# N-CW7_PWR_TWB.net
KiCad netlist of a schematic drawn in Altium Designer
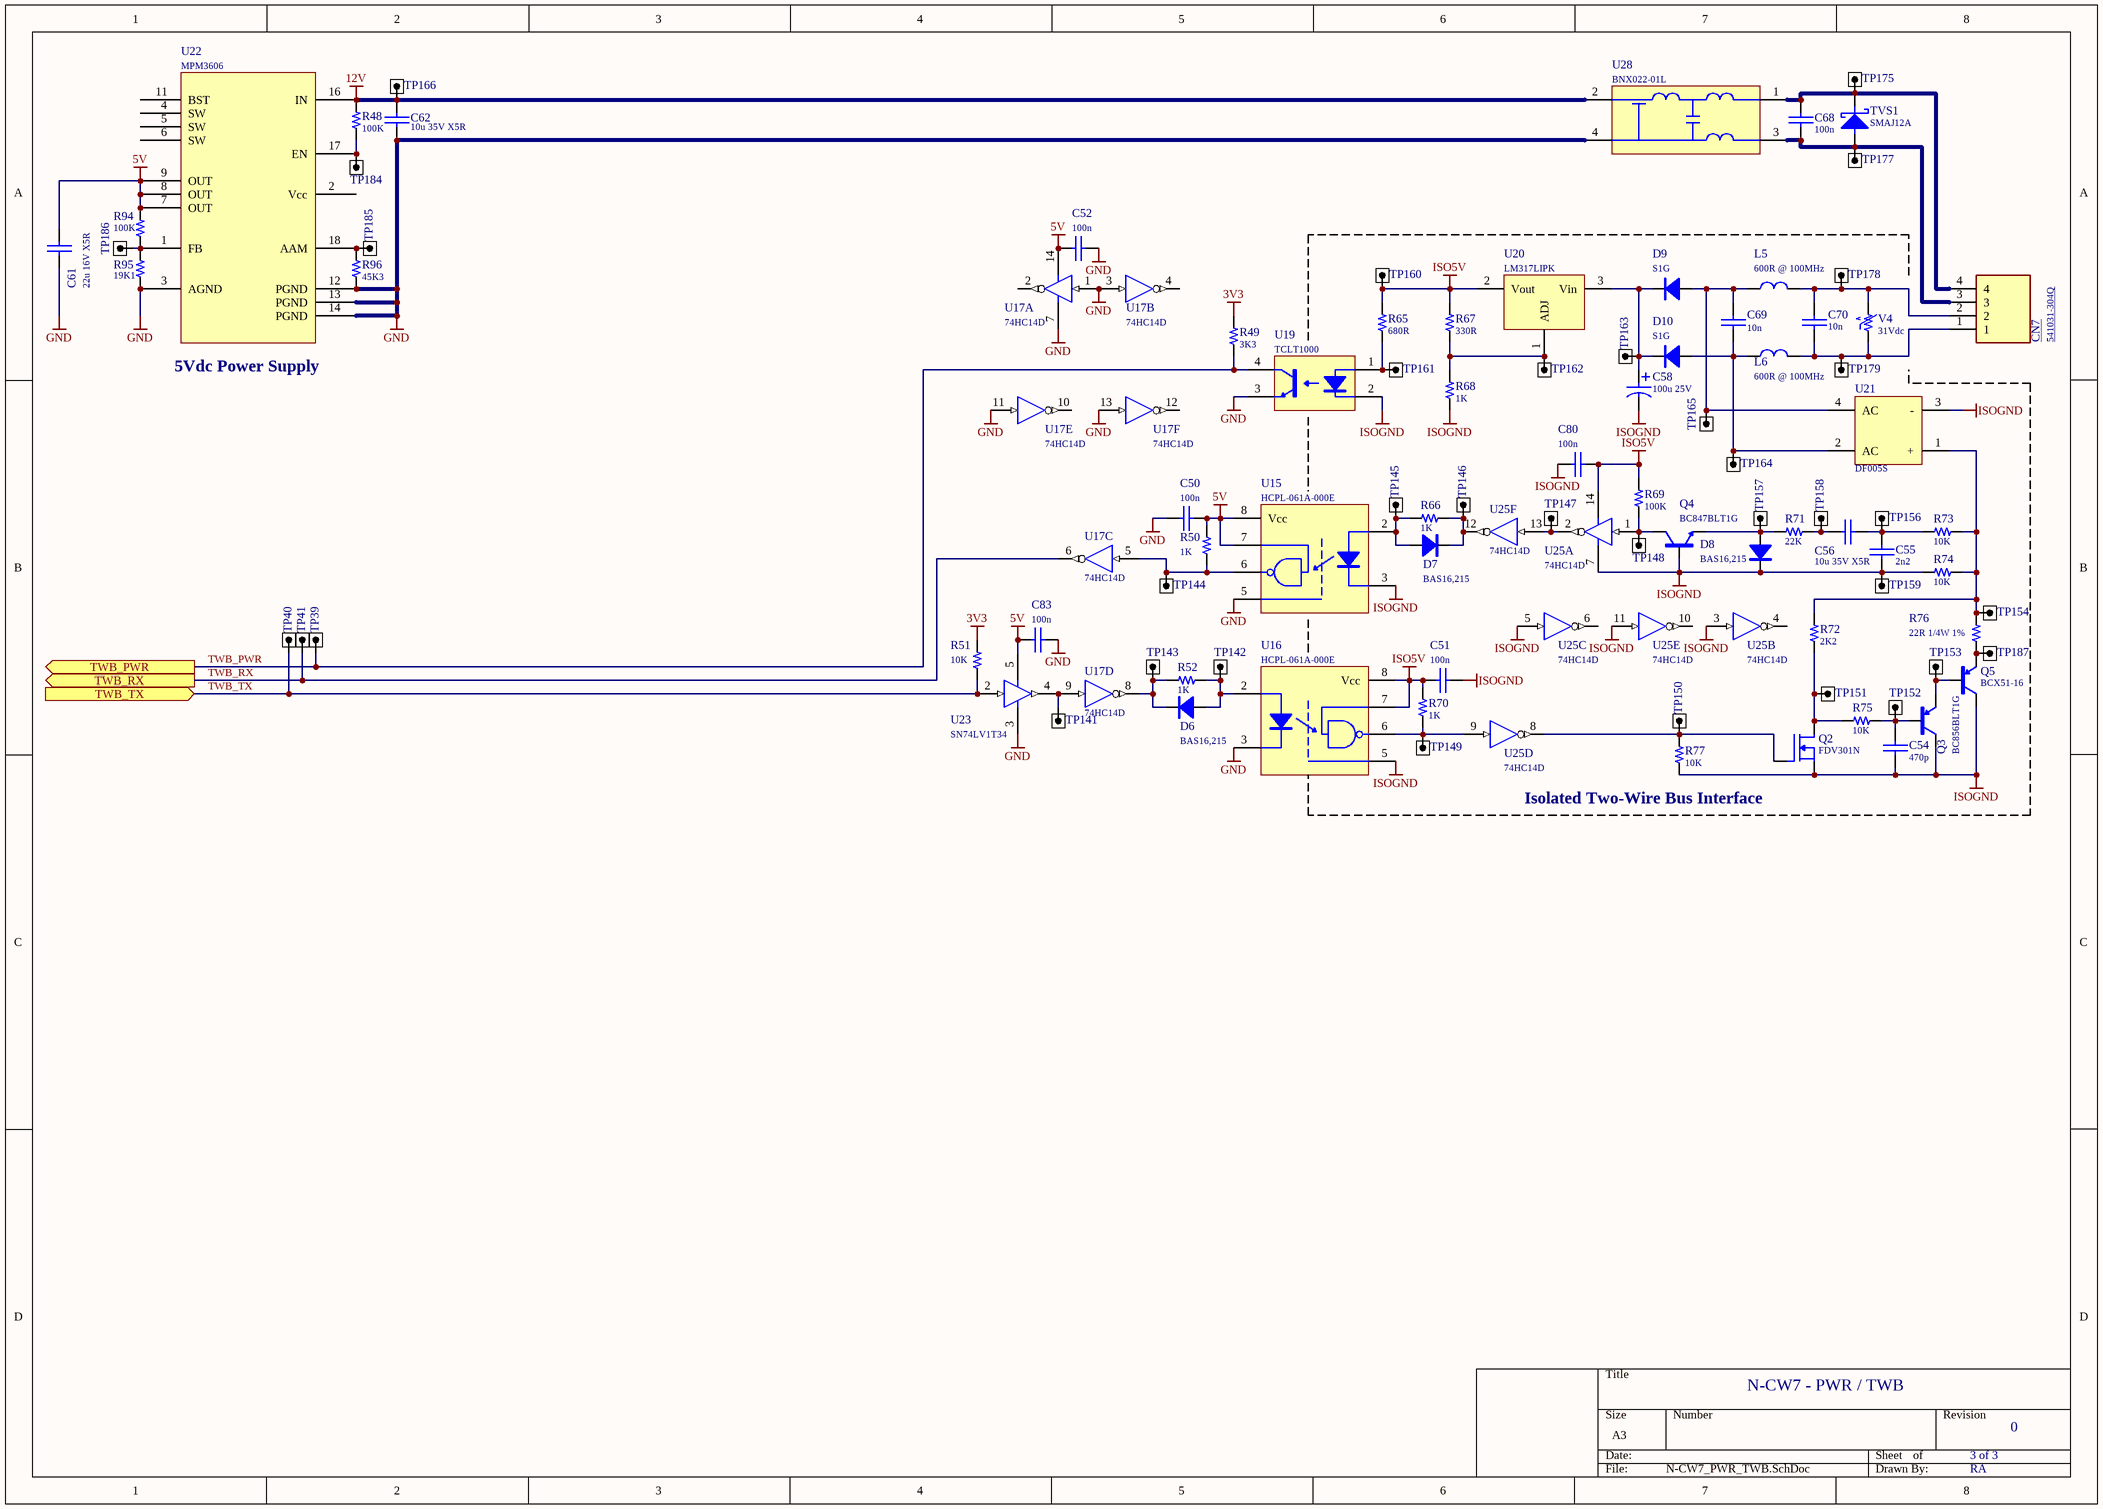
[diagram p0: N-CW7_PWR_TWB.SchDoc]

(export (version "E")
  (design (tool "Eeschema 10.0.6"))
  (components
    (comp (ref "C50")
      (value "100n")
      (footprint "TDK_0603_T0.80:CAPC1608X08N")
      (description "CAP CER 0.1UF 50V X7R 0603")
      (fields
        (field (name "MANUFACTURER") "TDK")
        (field (name "MANUFACTURER PART NUMBER") "C1608X7R1H104K080AA")
      )
      (libsource (lib "PassiveComponents_Capacitors_Ceramic") (part "TDK_0603_T0.80"))
    )
    (comp (ref "C51")
      (value "100n")
      (footprint "TDK_0603_T0.80:CAPC1608X08N")
      (description "CAP CER 0.1UF 50V X7R 0603")
      (fields
        (field (name "MANUFACTURER") "TDK")
        (field (name "MANUFACTURER PART NUMBER") "C1608X7R1H104K080AA")
      )
      (libsource (lib "PassiveComponents_Capacitors_Ceramic") (part "TDK_0603_T0.80"))
    )
    (comp (ref "C52")
      (value "100n")
      (footprint "TDK_0603_T0.80:CAPC1608X08N")
      (description "CAP CER 0.1UF 50V X7R 0603")
      (fields
        (field (name "MANUFACTURER") "TDK")
        (field (name "MANUFACTURER PART NUMBER") "C1608X7R1H104K080AA")
      )
      (libsource (lib "PassiveComponents_Capacitors_Ceramic") (part "TDK_0603_T0.80"))
    )
    (comp (ref "C54")
      (value "470p")
      (footprint "TDK_0603_T0.80:CAPC1608X08N")
      (description "CAP CER 470PF 50V C0G 0603")
      (fields
        (field (name "MANUFACTURER") "TDK")
        (field (name "MANUFACTURER PART NUMBER") "C1608C0G1H471J080AA")
      )
      (libsource (lib "PassiveComponents_Capacitors_Ceramic") (part "TDK_0603_T0.80"))
    )
    (comp (ref "C55")
      (value "2n2")
      (footprint "TDK_0603_T0.80:CAPC1608X08N")
      (description "CAP CER 2200PF 50V X7R 0603")
      (fields
        (field (name "MANUFACTURER") "TDK")
        (field (name "MANUFACTURER PART NUMBER") "C1608X7R1H222K080AE")
      )
      (libsource (lib "PassiveComponents_Capacitors_Ceramic") (part "TDK_0603_T0.80"))
    )
    (comp (ref "C56")
      (value "10u 35V X5R")
      (footprint "KEMET_1210_T1.90:CAPC3225X19N")
      (description "CAP CER 10UF 35V X5R 1210")
      (fields
        (field (name "MANUFACTURER") "KEMET")
        (field (name "MANUFACTURER PART NUMBER") "C1210C106K6PACTU")
      )
      (libsource (lib "PassiveComponents_Capacitors_Ceramic") (part "KEMET_1210_T1.90"))
    )
    (comp (ref "C58")
      (value "100u 25V")
      (footprint "KEMET_T494X/7343-43:CAPMP7343X43N")
      (description "CAP TANT 100UF 20% 25V 2917")
      (fields
        (field (name "MANUFACTURER") "KEMET")
        (field (name "MANUFACTURER PART NUMBER") "T494X107M025AT")
      )
      (libsource (lib "PassiveComponents_Capacitors_Tantalum") (part "KEMET_T494X/EIA7343-43"))
    )
    (comp (ref "C61")
      (value "22u 16V X5R")
      (footprint "TDK_0805_T1.25:CAPC2013X12N")
      (description "CAP CER 22UF 16V X5R 0805")
      (fields
        (field (name "MANUFACTURER") "TDK")
        (field (name "MANUFACTURER PART NUMBER") "C2012X5R1C226M085AC")
      )
      (libsource (lib "PassiveComponents_Capacitors_Ceramic") (part "TDK_0805_T1.25"))
    )
    (comp (ref "C62")
      (value "10u 35V X5R")
      (footprint "KEMET_1210_T1.90:CAPC3225X19N")
      (description "CAP CER 10UF 35V X5R 1210")
      (fields
        (field (name "MANUFACTURER") "KEMET")
        (field (name "MANUFACTURER PART NUMBER") "C1210C106K6PACTU")
      )
      (libsource (lib "PassiveComponents_Capacitors_Ceramic") (part "KEMET_1210_T1.90"))
    )
    (comp (ref "C68")
      (value "100n")
      (footprint "TDK_0603_T0.80:CAPC1608X08N")
      (description "CAP CER 0.1UF 50V X7R 0603")
      (fields
        (field (name "MANUFACTURER") "TDK")
        (field (name "MANUFACTURER PART NUMBER") "C1608X7R1H104K080AA")
      )
      (libsource (lib "PassiveComponents_Capacitors_Ceramic") (part "TDK_0603_T0.80"))
    )
    (comp (ref "C69")
      (value "10n")
      (footprint "TDK_0603_T0.80:CAPC1608X08N")
      (description "CAP CER 10000PF 50V X7R 0603")
      (fields
        (field (name "MANUFACTURER") "TDK")
        (field (name "MANUFACTURER PART NUMBER") "C1608X7R1H103K080AA")
      )
      (libsource (lib "PassiveComponents_Capacitors_Ceramic") (part "TDK_0603_T0.80"))
    )
    (comp (ref "C70")
      (value "10n")
      (footprint "TDK_0603_T0.80:CAPC1608X08N")
      (description "CAP CER 10000PF 50V X7R 0603")
      (fields
        (field (name "MANUFACTURER") "TDK")
        (field (name "MANUFACTURER PART NUMBER") "C1608X7R1H103K080AA")
      )
      (libsource (lib "PassiveComponents_Capacitors_Ceramic") (part "TDK_0603_T0.80"))
    )
    (comp (ref "C80")
      (value "100n")
      (footprint "TDK_0603_T0.80:CAPC1608X08N")
      (description "CAP CER 0.1UF 50V X7R 0603")
      (fields
        (field (name "MANUFACTURER") "TDK")
        (field (name "MANUFACTURER PART NUMBER") "C1608X7R1H104K080AA")
      )
      (libsource (lib "PassiveComponents_Capacitors_Ceramic") (part "TDK_0603_T0.80"))
    )
    (comp (ref "C83")
      (value "100n")
      (footprint "TDK_0603_T0.80:CAPC1608X08N")
      (description "CAP CER 0.1UF 50V X7R 0603")
      (fields
        (field (name "MANUFACTURER") "TDK")
        (field (name "MANUFACTURER PART NUMBER") "C1608X7R1H104K080AA")
      )
      (libsource (lib "PassiveComponents_Capacitors_Ceramic") (part "TDK_0603_T0.80"))
    )
    (comp (ref "CN7")
      (value "541031-304Q")
      (footprint "JWT_A2501WR2-4P:PS2.50MM")
      (description "A2501WR2-4P (JWT) 2.50mm Pitch (R-DIP)")
      (libsource (lib "Connectors") (part "JWT_A2501WR2-4P"))
    )
    (comp (ref "D6")
      (value "BAS16,215")
      (footprint "NEXPERIA_BAS16,215_SOT_23:SOT95P230X110-3N")
      (description "DIODE GP 100V 215MA SOT23")
      (fields (field (name "MANUFACTURER") "Nexperia"))
      (libsource (lib "DiscreteSemiconductors_Diodes_Rectifier") (part "NEXPERIA_BAS16,215_SOT23"))
    )
    (comp (ref "D7")
      (value "BAS16,215")
      (footprint "NEXPERIA_BAS16,215_SOT_23:SOT95P230X110-3N")
      (description "DIODE GP 100V 215MA SOT23")
      (fields (field (name "MANUFACTURER") "Nexperia"))
      (libsource (lib "DiscreteSemiconductors_Diodes_Rectifier") (part "NEXPERIA_BAS16,215_SOT23"))
    )
    (comp (ref "D8")
      (value "BAS16,215")
      (footprint "NEXPERIA_BAS16,215_SOT_23:SOT95P230X110-3N")
      (description "DIODE GP 100V 215MA SOT23")
      (fields (field (name "MANUFACTURER") "Nexperia"))
      (libsource (lib "DiscreteSemiconductors_Diodes_Rectifier") (part "NEXPERIA_BAS16,215_SOT23"))
    )
    (comp (ref "D9")
      (value "S1G")
      (footprint "DIODESINC_S1G_SMA_D0214AC:DIOM4326X24N")
      (description "DIODE GEN PURP 400V 1A SMA")
      (fields (field (name "MANUFACTURER") "Diodes") (field (name "MANUFACTURER PART NUMBER") "S1G-13-F"))
      (libsource (lib "DiscreteSemiconductors_Diodes_Rectifier") (part "DIODESINC_S1G_SMA_D0214AC"))
    )
    (comp (ref "D10")
      (value "S1G")
      (footprint "DIODESINC_S1G_SMA_D0214AC:DIOM4326X24N")
      (description "DIODE GEN PURP 400V 1A SMA")
      (fields (field (name "MANUFACTURER") "Diodes") (field (name "MANUFACTURER PART NUMBER") "S1G-13-F"))
      (libsource (lib "DiscreteSemiconductors_Diodes_Rectifier") (part "DIODESINC_S1G_SMA_D0214AC"))
    )
    (comp (ref "L5")
      (value "600R @ 100MHz")
      (footprint "LAIRD_MI0805K601R-10:INDC2012X09N")
      (description "FERRITE BEAD 600 OHM 0805 1LN")
      (fields
        (field (name "MANUFACTURER") "Laird")
        (field (name "MANUFACTURER PART NUMBER") "MI0805K601R-10")
      )
      (libsource (lib "PassiveComponents_Inductors") (part "LAIRD_MI0805K601R-10"))
    )
    (comp (ref "L6")
      (value "600R @ 100MHz")
      (footprint "LAIRD_MI0805K601R-10:INDC2012X09N")
      (description "FERRITE BEAD 600 OHM 0805 1LN")
      (fields
        (field (name "MANUFACTURER") "Laird")
        (field (name "MANUFACTURER PART NUMBER") "MI0805K601R-10")
      )
      (libsource (lib "PassiveComponents_Inductors") (part "LAIRD_MI0805K601R-10"))
    )
    (comp (ref "Q2")
      (value "FDV301N")
      (footprint "ONSEMI_FDV301N_SOT23:SOT95P230X110-3N")
      (description "MOSFET N-CH 25V 220MA SOT23")
      (fields (field (name "MANUFACTURER") "ON Semiconductor / Fairchild"))
      (libsource (lib "DiscreteSemiconductors_Transistors_JFETs") (part "ONSEMI_FDV301N_SOT23"))
    )
    (comp (ref "Q3")
      (value "BC856BLT1G")
      (footprint "ONSEMI_BC856BLT1G_SOT23_SOT95P237X110-3N")
      (description "TRANS PNP 65V 100MA SOT23-3")
      (fields (field (name "MANUFACTURER") "ON Semiconductor"))
      (libsource (lib "DiscreteSemiconductors_Transistors_BJTs") (part "ONSEMI_BC856BLT1G_SOT23"))
    )
    (comp (ref "Q4")
      (value "BC847BLT1G")
      (footprint "ONSEMI_BC847BLT1G_SOT23:SOT95P230X110-3N")
      (description "TRANS NPN 45V 100MA SOT23-3")
      (fields (field (name "MANUFACTURER") "ON Semiconductor"))
      (libsource (lib "DiscreteSemiconductors_Transistors_BJTs") (part "ONSEMI_BC847BLT1G_SOT23"))
    )
    (comp (ref "Q5")
      (value "BCX51-16")
      (footprint "INFINEON_BCX51-16_SOT89:SOT89-150P400X150-3N")
      (description "Bipolar (BJT) Transistor PNP 45 V 1 A 125MHz 2 W Surface Mount PG-SOT89")
      (fields (field (name "MANUFACTURER") "Infineon"))
      (libsource (lib "DiscreteSemiconductors_Transistors_BJTs") (part "INFINEON_BCX51-16_SOT89"))
    )
    (comp (ref "R48")
      (value "100K")
      (footprint "YAGEO_0603_T0.55:RESC1608X06N")
      (description "RES 100K OHM 1% 1/10W 0603")
      (fields
        (field (name "MANUFACTURER") "Yageo")
        (field (name "MANUFACTURER PART NUMBER") "RC0603FR-07100KL")
      )
      (libsource (lib "PassiveComponents_Resistors_ChipSMD") (part "YAGEO_0603_T0.55"))
    )
    (comp (ref "R49")
      (value "3K3")
      (footprint "YAGEO_0603_T0.55:RESC1608X06N")
      (description "RC0603FR-07XXXL")
      (fields
        (field (name "MANUFACTURER") "Yageo")
        (field (name "MANUFACTURER PART NUMBER") "RC0603FR-073K3L")
      )
      (libsource (lib "PassiveComponents_Resistors_ChipSMD") (part "YAGEO_0603_T0.55"))
    )
    (comp (ref "R50")
      (value "1K")
      (footprint "YAGEO_0603_T0.55:RESC1608X06N")
      (description "RES 1K OHM 1% 1/10W 0603")
      (fields
        (field (name "MANUFACTURER") "Yageo")
        (field (name "MANUFACTURER PART NUMBER") "RC0603FR-071KL")
      )
      (libsource (lib "PassiveComponents_Resistors_ChipSMD") (part "YAGEO_0603_T0.55"))
    )
    (comp (ref "R51")
      (value "10K")
      (footprint "YAGEO_0603_T0.55:RESC1608X06N")
      (description "RES 10K OHM 1% 1/10W 0603")
      (fields
        (field (name "MANUFACTURER") "Yageo")
        (field (name "MANUFACTURER PART NUMBER") "RC0603FR-0710KL")
      )
      (libsource (lib "PassiveComponents_Resistors_ChipSMD") (part "YAGEO_0603_T0.55"))
    )
    (comp (ref "R52")
      (value "1K")
      (footprint "YAGEO_0603_T0.55:RESC1608X06N")
      (description "RES 1K OHM 1% 1/10W 0603")
      (fields
        (field (name "MANUFACTURER") "Yageo")
        (field (name "MANUFACTURER PART NUMBER") "RC0603FR-071KL")
      )
      (libsource (lib "PassiveComponents_Resistors_ChipSMD") (part "YAGEO_0603_T0.55"))
    )
    (comp (ref "R65")
      (value "680R")
      (footprint "YAGEO_0603_T0.55:RESC1608X06N")
      (description "RES 680 OHM 1% 1/10W 0603")
      (fields
        (field (name "MANUFACTURER") "Yageo")
        (field (name "MANUFACTURER PART NUMBER") "RC0603FR-07680RL")
      )
      (libsource (lib "PassiveComponents_Resistors_ChipSMD") (part "YAGEO_0603_T0.55"))
    )
    (comp (ref "R66")
      (value "1K")
      (footprint "YAGEO_0603_T0.55:RESC1608X06N")
      (description "RES 1K OHM 1% 1/10W 0603")
      (fields
        (field (name "MANUFACTURER") "Yageo")
        (field (name "MANUFACTURER PART NUMBER") "RC0603FR-071KL")
      )
      (libsource (lib "PassiveComponents_Resistors_ChipSMD") (part "YAGEO_0603_T0.55"))
    )
    (comp (ref "R67")
      (value "330R")
      (footprint "YAGEO_0603_T0.55:RESC1608X06N")
      (description "RES 330 OHM 1% 1/10W 0603")
      (fields
        (field (name "MANUFACTURER") "Yageo")
        (field (name "MANUFACTURER PART NUMBER") "RC0603FR-07330RL")
      )
      (libsource (lib "PassiveComponents_Resistors_ChipSMD") (part "YAGEO_0603_T0.55"))
    )
    (comp (ref "R68")
      (value "1K")
      (footprint "YAGEO_0603_T0.55:RESC1608X06N")
      (description "RES 1K OHM 1% 1/10W 0603")
      (fields
        (field (name "MANUFACTURER") "Yageo")
        (field (name "MANUFACTURER PART NUMBER") "RC0603FR-071KL")
      )
      (libsource (lib "PassiveComponents_Resistors_ChipSMD") (part "YAGEO_0603_T0.55"))
    )
    (comp (ref "R69")
      (value "100K")
      (footprint "YAGEO_0603_T0.55:RESC1608X06N")
      (description "RES 100K OHM 1% 1/10W 0603")
      (fields
        (field (name "MANUFACTURER") "Yageo")
        (field (name "MANUFACTURER PART NUMBER") "RC0603FR-07100KL")
      )
      (libsource (lib "PassiveComponents_Resistors_ChipSMD") (part "YAGEO_0603_T0.55"))
    )
    (comp (ref "R70")
      (value "1K")
      (footprint "YAGEO_0603_T0.55:RESC1608X06N")
      (description "RES 1K OHM 1% 1/10W 0603")
      (fields
        (field (name "MANUFACTURER") "Yageo")
        (field (name "MANUFACTURER PART NUMBER") "RC0603FR-071KL")
      )
      (libsource (lib "PassiveComponents_Resistors_ChipSMD") (part "YAGEO_0603_T0.55"))
    )
    (comp (ref "R71")
      (value "22K")
      (footprint "YAGEO_0603_T0.55:RESC1608X06N")
      (description "RES 22K OHM 1% 1/10W 0603")
      (fields
        (field (name "MANUFACTURER") "Yageo")
        (field (name "MANUFACTURER PART NUMBER") "RC0603FR-0722KL")
      )
      (libsource (lib "PassiveComponents_Resistors_ChipSMD") (part "YAGEO_0603_T0.55"))
    )
    (comp (ref "R72")
      (value "2K2")
      (footprint "YAGEO_0603_T0.55:RESC1608X06N")
      (description "RES 2.2K OHM 1% 1/10W 0603")
      (fields
        (field (name "MANUFACTURER") "Yageo")
        (field (name "MANUFACTURER PART NUMBER") "RC0603FR-072K2L")
      )
      (libsource (lib "PassiveComponents_Resistors_ChipSMD") (part "YAGEO_0603_T0.55"))
    )
    (comp (ref "R73")
      (value "10K")
      (footprint "YAGEO_0603_T0.55:RESC1608X06N")
      (description "RES 10K OHM 1% 1/10W 0603")
      (fields
        (field (name "MANUFACTURER") "Yageo")
        (field (name "MANUFACTURER PART NUMBER") "RC0603FR-0710KL")
      )
      (libsource (lib "PassiveComponents_Resistors_ChipSMD") (part "YAGEO_0603_T0.55"))
    )
    (comp (ref "R74")
      (value "10K")
      (footprint "YAGEO_0603_T0.55:RESC1608X06N")
      (description "RES 10K OHM 1% 1/10W 0603")
      (fields
        (field (name "MANUFACTURER") "Yageo")
        (field (name "MANUFACTURER PART NUMBER") "RC0603FR-0710KL")
      )
      (libsource (lib "PassiveComponents_Resistors_ChipSMD") (part "YAGEO_0603_T0.55"))
    )
    (comp (ref "R75")
      (value "10K")
      (footprint "YAGEO_0603_T0.55:RESC1608X06N")
      (description "RES 10K OHM 1% 1/10W 0603")
      (fields
        (field (name "MANUFACTURER") "Yageo")
        (field (name "MANUFACTURER PART NUMBER") "RC0603FR-0710KL")
      )
      (libsource (lib "PassiveComponents_Resistors_ChipSMD") (part "YAGEO_0603_T0.55"))
    )
    (comp (ref "R76")
      (value "22R 1/4W 1%")
      (footprint "YAGEO_1206_T0.55:RESC3116X06N")
      (description "RES 22 OHM 1% 1/4W 1206")
      (fields
        (field (name "MANUFACTURER") "Yageo")
        (field (name "MANUFACTURER PART NUMBER") "RC1206FR-0722RL")
      )
      (libsource (lib "PassiveComponents_Resistors_ChipSMD") (part "YAGEO_1206_T0.55"))
    )
    (comp (ref "R77")
      (value "10K")
      (footprint "YAGEO_0603_T0.55:RESC1608X06N")
      (description "RES 10K OHM 1% 1/10W 0603")
      (fields
        (field (name "MANUFACTURER") "Yageo")
        (field (name "MANUFACTURER PART NUMBER") "RC0603FR-0710KL")
      )
      (libsource (lib "PassiveComponents_Resistors_ChipSMD") (part "YAGEO_0603_T0.55"))
    )
    (comp (ref "R94")
      (value "100K")
      (footprint "YAGEO_0603_T0.55:RESC1608X06N")
      (description "RES 100K OHM 1% 1/10W 0603")
      (fields
        (field (name "MANUFACTURER") "Yageo")
        (field (name "MANUFACTURER PART NUMBER") "RC0603FR-07100KL")
      )
      (libsource (lib "PassiveComponents_Resistors_ChipSMD") (part "YAGEO_0603_T0.55"))
    )
    (comp (ref "R95")
      (value "19K1")
      (footprint "YAGEO_0603_T0.55:RESC1608X06N")
      (description "RES 19.1K OHM 1% 1/10W 0603")
      (fields
        (field (name "MANUFACTURER") "Yageo")
        (field (name "MANUFACTURER PART NUMBER") "RC0603FR-0719K1L")
      )
      (libsource (lib "PassiveComponents_Resistors_ChipSMD") (part "YAGEO_0603_T0.55"))
    )
    (comp (ref "R96")
      (value "45K3")
      (footprint "YAGEO_0603_T0.55:RESC1608X06N")
      (description "RES 45.3K OHM 1% 1/10W 0603")
      (fields
        (field (name "MANUFACTURER") "Yageo")
        (field (name "MANUFACTURER PART NUMBER") "RC0603FR-0745K3L")
      )
      (libsource (lib "PassiveComponents_Resistors_ChipSMD") (part "YAGEO_0603_T0.55"))
    )
    (comp (ref "TP39")
      (value "TESTPOINT_OCTAGONAL")
      (footprint "TESTPOINT_OCTAGONAL")
      (libsource (lib "") (part "TESTPOINT_OCTAGONAL_2"))
    )
    (comp (ref "TP40")
      (value "TESTPOINT_OCTAGONAL")
      (footprint "TESTPOINT_OCTAGONAL")
      (libsource (lib "") (part "TESTPOINT_OCTAGONAL_2"))
    )
    (comp (ref "TP41")
      (value "TESTPOINT_OCTAGONAL")
      (footprint "TESTPOINT_OCTAGONAL")
      (libsource (lib "") (part "TESTPOINT_OCTAGONAL_2"))
    )
    (comp (ref "TP141")
      (value "TESTPOINT_OCTAGONAL")
      (footprint "TESTPOINT_OCTAGONAL")
      (libsource (lib "") (part "TESTPOINT_OCTAGONAL_1"))
    )
    (comp (ref "TP142")
      (value "TESTPOINT_OCTAGONAL")
      (footprint "TESTPOINT_OCTAGONAL")
      (libsource (lib "") (part "TESTPOINT_OCTAGONAL_2"))
    )
    (comp (ref "TP143")
      (value "TESTPOINT_OCTAGONAL")
      (footprint "TESTPOINT_OCTAGONAL")
      (libsource (lib "") (part "TESTPOINT_OCTAGONAL_2"))
    )
    (comp (ref "TP144")
      (value "TESTPOINT_OCTAGONAL")
      (footprint "TESTPOINT_OCTAGONAL")
      (libsource (lib "") (part "TESTPOINT_OCTAGONAL_1"))
    )
    (comp (ref "TP145")
      (value "TESTPOINT_OCTAGONAL")
      (footprint "TESTPOINT_OCTAGONAL")
      (libsource (lib "") (part "TESTPOINT_OCTAGONAL_2"))
    )
    (comp (ref "TP146")
      (value "TESTPOINT_OCTAGONAL")
      (footprint "TESTPOINT_OCTAGONAL")
      (libsource (lib "") (part "TESTPOINT_OCTAGONAL_2"))
    )
    (comp (ref "TP147")
      (value "TESTPOINT_OCTAGONAL")
      (footprint "TESTPOINT_OCTAGONAL")
      (libsource (lib "") (part "TESTPOINT_OCTAGONAL_2"))
    )
    (comp (ref "TP148")
      (value "TESTPOINT_OCTAGONAL")
      (footprint "TESTPOINT_OCTAGONAL")
      (libsource (lib "") (part "TESTPOINT_OCTAGONAL_1"))
    )
    (comp (ref "TP149")
      (value "TESTPOINT_OCTAGONAL")
      (footprint "TESTPOINT_OCTAGONAL")
      (libsource (lib "") (part "TESTPOINT_OCTAGONAL_1"))
    )
    (comp (ref "TP150")
      (value "TESTPOINT_OCTAGONAL")
      (footprint "TESTPOINT_OCTAGONAL")
      (libsource (lib "") (part "TESTPOINT_OCTAGONAL_2"))
    )
    (comp (ref "TP151")
      (value "TESTPOINT_OCTAGONAL")
      (footprint "TESTPOINT_OCTAGONAL")
      (libsource (lib "Miscellaneous") (part "TESTPOINT_OCTAGONAL"))
    )
    (comp (ref "TP152")
      (value "TESTPOINT_OCTAGONAL")
      (footprint "TESTPOINT_OCTAGONAL")
      (libsource (lib "") (part "TESTPOINT_OCTAGONAL_2"))
    )
    (comp (ref "TP153")
      (value "TESTPOINT_OCTAGONAL")
      (footprint "TESTPOINT_OCTAGONAL")
      (libsource (lib "") (part "TESTPOINT_OCTAGONAL_2"))
    )
    (comp (ref "TP154")
      (value "TESTPOINT_OCTAGONAL")
      (footprint "TESTPOINT_OCTAGONAL")
      (libsource (lib "Miscellaneous") (part "TESTPOINT_OCTAGONAL"))
    )
    (comp (ref "TP156")
      (value "TESTPOINT_OCTAGONAL")
      (footprint "TESTPOINT_OCTAGONAL")
      (libsource (lib "") (part "TESTPOINT_OCTAGONAL_2"))
    )
    (comp (ref "TP157")
      (value "TESTPOINT_OCTAGONAL")
      (footprint "TESTPOINT_OCTAGONAL")
      (libsource (lib "") (part "TESTPOINT_OCTAGONAL_2"))
    )
    (comp (ref "TP158")
      (value "TESTPOINT_OCTAGONAL")
      (footprint "TESTPOINT_OCTAGONAL")
      (libsource (lib "") (part "TESTPOINT_OCTAGONAL_2"))
    )
    (comp (ref "TP159")
      (value "TESTPOINT_OCTAGONAL")
      (footprint "TESTPOINT_OCTAGONAL")
      (libsource (lib "") (part "TESTPOINT_OCTAGONAL_1"))
    )
    (comp (ref "TP160")
      (value "TESTPOINT_OCTAGONAL")
      (footprint "TESTPOINT_OCTAGONAL")
      (libsource (lib "") (part "TESTPOINT_OCTAGONAL_2"))
    )
    (comp (ref "TP161")
      (value "TESTPOINT_OCTAGONAL")
      (footprint "TESTPOINT_OCTAGONAL")
      (libsource (lib "Miscellaneous") (part "TESTPOINT_OCTAGONAL"))
    )
    (comp (ref "TP162")
      (value "TESTPOINT_OCTAGONAL")
      (footprint "TESTPOINT_OCTAGONAL")
      (libsource (lib "") (part "TESTPOINT_OCTAGONAL_1"))
    )
    (comp (ref "TP163")
      (value "TESTPOINT_OCTAGONAL")
      (footprint "TESTPOINT_OCTAGONAL")
      (libsource (lib "") (part "TESTPOINT_OCTAGONAL_3"))
    )
    (comp (ref "TP164")
      (value "TESTPOINT_OCTAGONAL")
      (footprint "TESTPOINT_OCTAGONAL")
      (libsource (lib "") (part "TESTPOINT_OCTAGONAL_1"))
    )
    (comp (ref "TP165")
      (value "TESTPOINT_OCTAGONAL")
      (footprint "TESTPOINT_OCTAGONAL")
      (libsource (lib "") (part "TESTPOINT_OCTAGONAL_1"))
    )
    (comp (ref "TP166")
      (value "TESTPOINT_OCTAGONAL")
      (footprint "TESTPOINT_OCTAGONAL")
      (libsource (lib "") (part "TESTPOINT_OCTAGONAL_2"))
    )
    (comp (ref "TP175")
      (value "TESTPOINT_OCTAGONAL")
      (footprint "TESTPOINT_OCTAGONAL")
      (libsource (lib "") (part "TESTPOINT_OCTAGONAL_2"))
    )
    (comp (ref "TP177")
      (value "TESTPOINT_OCTAGONAL")
      (footprint "TESTPOINT_OCTAGONAL")
      (libsource (lib "") (part "TESTPOINT_OCTAGONAL_1"))
    )
    (comp (ref "TP178")
      (value "TESTPOINT_OCTAGONAL")
      (footprint "TESTPOINT_OCTAGONAL")
      (libsource (lib "") (part "TESTPOINT_OCTAGONAL_2"))
    )
    (comp (ref "TP179")
      (value "TESTPOINT_OCTAGONAL")
      (footprint "TESTPOINT_OCTAGONAL")
      (libsource (lib "") (part "TESTPOINT_OCTAGONAL_1"))
    )
    (comp (ref "TP184")
      (value "TESTPOINT_OCTAGONAL")
      (footprint "TESTPOINT_OCTAGONAL")
      (libsource (lib "") (part "TESTPOINT_OCTAGONAL_1"))
    )
    (comp (ref "TP185")
      (value "TESTPOINT_OCTAGONAL")
      (footprint "TESTPOINT_OCTAGONAL")
      (libsource (lib "Miscellaneous") (part "TESTPOINT_OCTAGONAL"))
    )
    (comp (ref "TP186")
      (value "TESTPOINT_OCTAGONAL")
      (footprint "TESTPOINT_OCTAGONAL")
      (libsource (lib "") (part "TESTPOINT_OCTAGONAL_3"))
    )
    (comp (ref "TP187")
      (value "TESTPOINT_OCTAGONAL")
      (footprint "TESTPOINT_OCTAGONAL")
      (libsource (lib "Miscellaneous") (part "TESTPOINT_OCTAGONAL"))
    )
    (comp (ref "TVS1")
      (value "SMAJ12A")
      (footprint "LITTELFUSE_SMAJ12A_D0214AC:DIOM4326X23N")
      (description "TVS DIODE 12VWM 19.9VC DO214AC")
      (fields (field (name "MANUFACTURER") "Littelfuse"))
      (libsource (lib "CircuitProtection_TVSDiodes") (part "LITTELFUSE_SMAJ12A_D0214AC"))
    )
    (comp (ref "U15")
      (value "HCPL-061A-000E")
      (footprint "BROADCOM_HCPL-061A-000E:SOIC127P600X338-8N")
      (description "OPTOISO 3.75KV OPN COLL 8SO TALL")
      (fields (field (name "MANUFACTURER") "Broadcom Avago"))
      (libsource (lib "") (part "BROADCOM_HCPL-061A-000E_1"))
    )
    (comp (ref "U16")
      (value "HCPL-061A-000E")
      (footprint "BROADCOM_HCPL-061A-000E:SOIC127P600X338-8N")
      (description "OPTOISO 3.75KV OPN COLL 8SO TALL")
      (fields (field (name "MANUFACTURER") "Broadcom Avago"))
      (libsource (lib "OptoElectronics_OptoCouplers") (part "BROADCOM_HCPL-061A-000E"))
    )
    (comp (ref "U17")
      (value "74HC14D")
      (footprint "NEXPERIA_74HC14D_SO14:SOIC127P600X175-14N")
      (description "IC HEX INVERTER SCHM TRIG 14SOIC")
      (fields
        (field (name "MANUFACTURER") "Nexperia")
        (field (name "MANUFACTURER PART NUMBER") "74HC14D,653")
      )
      (libsource (lib "IntegratedCircuits_Logic_Gates") (part "NEXPERIA_74HC14D_SO14"))
    )
    (comp (ref "U19")
      (value "TCLT1000")
      (footprint "VISHAY_TCLT1000_SOP4L:SOP254P1020X230-4N")
      (description "OPTOISOLATOR 5KV 1CH TRANS 4-SOP")
      (fields (field (name "MANUFACTURER") "Vishay"))
      (libsource (lib "OptoElectronics_OptoCouplers") (part "VISHAY_TCLT1000_SOP4L"))
    )
    (comp (ref "U20")
      (value "LM317LIPK")
      (footprint "TI_LM317LIPK_SOT89:SOT89-150P350X160-3N")
      (description "IC REG LIN POS ADJ 100MA SOT89-3")
      (fields (field (name "MANUFACTURER") "Texas Instruments"))
      (libsource (lib "IntegratedCircuits_Power_VoltageRegsLinear") (part "TI_LM317LIPK_SOT89"))
    )
    (comp (ref "U21")
      (value "DF005S")
      (footprint "DIODESINC_DF005S:SOP520P1040X265-4N")
      (description "BRIDGE RECT 1PHASE 50V 1A DFS")
      (fields (field (name "MANUFACTURER") "Diodes"))
      (libsource (lib "DiscreteSemiconductors_Diodes_Rectifier") (part "DIODESINC_DF005S"))
    )
    (comp (ref "U22")
      (value "MPM3606")
      (footprint "MPS_MPM3606GQV-P")
      (description "DC DC CONVERTER 0.8-5.5V")
      (fields
        (field (name "MANUFACTURER") "Monolithic Power Systems")
        (field (name "MANUFACTURER PART NUMBER") "MPM3606GQV-P")
      )
      (libsource (lib "IntegratedCircuits_Power_VoltageRegsSwitchMode") (part "MPS_MPM3606GQV-P"))
    )
    (comp (ref "U23")
      (value "SN74LV1T34")
      (footprint "TI_SN74LV1T34_SOT23_5:SOT95P280X145-5N")
      (description "IC BUF NON-INVERT 5.5V SOT23-5")
      (fields
        (field (name "MANUFACTURER") "Texas Instruments")
        (field (name "MANUFACTURER PART NUMBER") "SN74LV1T34DBVR")
      )
      (libsource (lib "IntegratedCircuits_Logic_Gates") (part "TI_SN74LV1T34_SOT23_5"))
    )
    (comp (ref "U25")
      (value "74HC14D")
      (footprint "NEXPERIA_74HC14D_SO14:SOIC127P600X175-14N")
      (description "IC HEX INVERTER SCHM TRIG 14SOIC")
      (fields
        (field (name "MANUFACTURER") "Nexperia")
        (field (name "MANUFACTURER PART NUMBER") "74HC14D,653")
      )
      (libsource (lib "IntegratedCircuits_Logic_Gates") (part "NEXPERIA_74HC14D_SO14"))
    )
    (comp (ref "U28")
      (value "BNX022-01L")
      (footprint "MURATA_BNX022-01L")
      (description "FILTER LC 1UF SMD")
      (fields (field (name "MANUFACTURER") "Murata"))
      (libsource (lib "PassiveComponents_LCFilters") (part "MURATA_BNX022-01L"))
    )
    (comp (ref "V4")
      (value "31Vdc")
      (footprint "TDK_B72520_1206:INDC3216X17N")
      (description "VARISTOR 39V 200A 1206")
      (fields
        (field (name "MANUFACTURER") "TDK EPCOS")
        (field (name "MANUFACTURER PART NUMBER") "B72520T0250K062")
      )
      (libsource (lib "CircuitProtection_Varistors") (part "TDK_B72520_1206"))
    )
  )
  (nets
    (net (code "1") (name "/TWB_PWR") (class "Default")
      (node (ref "R49") (pin "1") (pinfunction "1_1") (pintype "passive"))
      (node (ref "TP39") (pin "1") (pinfunction "1_1") (pintype "passive"))
      (node (ref "U19") (pin "4") (pinfunction "4_4") (pintype "passive"))
    )
    (net (code "2") (name "/TWB_RX") (class "Default")
      (node (ref "TP41") (pin "1") (pinfunction "1_1") (pintype "passive"))
      (node (ref "U17") (pin "6") (pinfunction "Y3_6") (pintype "output"))
    )
    (net (code "3") (name "/TWB_TX") (class "Default")
      (node (ref "R51") (pin "2") (pinfunction "2_2") (pintype "passive"))
      (node (ref "TP40") (pin "1") (pinfunction "1_1") (pintype "passive"))
      (node (ref "U23") (pin "2") (pinfunction "A_2") (pintype "input"))
    )
    (net (code "4") (name "3V3") (class "Default")
      (node (ref "R49") (pin "2") (pinfunction "2_2") (pintype "passive"))
      (node (ref "R51") (pin "1") (pinfunction "1_1") (pintype "passive"))
    )
    (net (code "5") (name "5V") (class "Default")
      (node (ref "C50") (pin "2") (pinfunction "2_2") (pintype "passive"))
      (node (ref "C52") (pin "1") (pinfunction "1_1") (pintype "passive"))
      (node (ref "C61") (pin "2") (pinfunction "2_2") (pintype "passive"))
      (node (ref "C83") (pin "1") (pinfunction "1_1") (pintype "passive"))
      (node (ref "R50") (pin "1") (pinfunction "1_1") (pintype "passive"))
      (node (ref "R94") (pin "1") (pinfunction "1_1") (pintype "passive"))
      (node (ref "U15") (pin "7") (pintype "passive"))
      (node (ref "U15") (pin "8") (pinfunction "Vcc_8") (pintype "power_in"))
      (node (ref "U17") (pin "14") (pinfunction "Vcc_14") (pintype "power_in"))
      (node (ref "U22") (pin "7") (pinfunction "OUT_7") (pintype "passive"))
      (node (ref "U22") (pin "8") (pinfunction "OUT_8") (pintype "passive"))
      (node (ref "U22") (pin "9") (pinfunction "OUT_9") (pintype "passive"))
      (node (ref "U23") (pin "5") (pinfunction "Vcc_5") (pintype "power_in"))
    )
    (net (code "6") (name "12V") (class "Default")
      (node (ref "C62") (pin "2") (pinfunction "2_2") (pintype "passive"))
      (node (ref "R48") (pin "1") (pinfunction "1_1") (pintype "passive"))
      (node (ref "TP166") (pin "1") (pinfunction "1_1") (pintype "passive"))
      (node (ref "U22") (pin "16") (pinfunction "IN_16") (pintype "passive"))
      (node (ref "U28") (pin "2") (pinfunction "CB_2") (pintype "passive"))
    )
    (net (code "7") (name "GND") (class "Default")
      (node (ref "C50") (pin "1") (pinfunction "1_1") (pintype "passive"))
      (node (ref "C52") (pin "2") (pinfunction "2_2") (pintype "passive"))
      (node (ref "C61") (pin "1") (pinfunction "1_1") (pintype "passive"))
      (node (ref "C62") (pin "1") (pinfunction "1_1") (pintype "passive"))
      (node (ref "C83") (pin "2") (pinfunction "2_2") (pintype "passive"))
      (node (ref "R95") (pin "2") (pinfunction "2_2") (pintype "passive"))
      (node (ref "R96") (pin "1") (pinfunction "1_1") (pintype "passive"))
      (node (ref "U15") (pin "5") (pintype "power_in"))
      (node (ref "U16") (pin "3") (pintype "passive"))
      (node (ref "U17") (pin "1") (pinfunction "A1_1") (pintype "input"))
      (node (ref "U17") (pin "11") (pinfunction "A5_11") (pintype "input"))
      (node (ref "U17") (pin "13") (pinfunction "A6_13") (pintype "input"))
      (node (ref "U17") (pin "3") (pinfunction "A2_3") (pintype "input"))
      (node (ref "U17") (pin "7") (pinfunction "GND_7") (pintype "power_in"))
      (node (ref "U19") (pin "3") (pinfunction "3_3") (pintype "passive"))
      (node (ref "U22") (pin "12") (pinfunction "PGND_12") (pintype "passive"))
      (node (ref "U22") (pin "13") (pinfunction "PGND_13") (pintype "passive"))
      (node (ref "U22") (pin "14") (pinfunction "PGND_14") (pintype "passive"))
      (node (ref "U22") (pin "3") (pinfunction "AGND_3") (pintype "passive"))
      (node (ref "U23") (pin "3") (pinfunction "GND_3") (pintype "power_in"))
      (node (ref "U28") (pin "4") (pinfunction "CG_4") (pintype "passive"))
    )
    (net (code "8") (name "ISO5V") (class "Default")
      (node (ref "C51") (pin "1") (pinfunction "1_1") (pintype "passive"))
      (node (ref "C80") (pin "2") (pinfunction "2_2") (pintype "passive"))
      (node (ref "R65") (pin "2") (pinfunction "2_2") (pintype "passive"))
      (node (ref "R67") (pin "1") (pinfunction "1_1") (pintype "passive"))
      (node (ref "R69") (pin "1") (pinfunction "1_1") (pintype "passive"))
      (node (ref "R70") (pin "1") (pinfunction "1_1") (pintype "passive"))
      (node (ref "TP160") (pin "1") (pinfunction "1_1") (pintype "passive"))
      (node (ref "U16") (pin "7") (pintype "passive"))
      (node (ref "U16") (pin "8") (pinfunction "Vcc_8") (pintype "power_in"))
      (node (ref "U20") (pin "2") (pinfunction "Vout_2") (pintype "passive"))
      (node (ref "U25") (pin "14") (pinfunction "Vcc_14") (pintype "power_in"))
    )
    (net (code "9") (name "ISOGND") (class "Default")
      (node (ref "C51") (pin "2") (pinfunction "2_2") (pintype "passive"))
      (node (ref "C54") (pin "1") (pinfunction "1_1") (pintype "passive"))
      (node (ref "C55") (pin "1") (pinfunction "1_1") (pintype "passive"))
      (node (ref "C58") (pin "2") (pinfunction "2_2") (pintype "passive"))
      (node (ref "C80") (pin "1") (pinfunction "1_1") (pintype "passive"))
      (node (ref "D8") (pin "3") (pinfunction "K_3") (pintype "passive"))
      (node (ref "Q2") (pin "2") (pinfunction "S_2") (pintype "passive"))
      (node (ref "Q3") (pin "3") (pinfunction "C_3") (pintype "passive"))
      (node (ref "Q4") (pin "1") (pinfunction "B_1") (pintype "passive"))
      (node (ref "Q5") (pin "2") (pinfunction "C_2") (pintype "passive"))
      (node (ref "R68") (pin "2") (pinfunction "2_2") (pintype "passive"))
      (node (ref "R74") (pin "1") (pinfunction "1_1") (pintype "passive"))
      (node (ref "R77") (pin "1") (pinfunction "1_1") (pintype "passive"))
      (node (ref "TP159") (pin "1") (pinfunction "1_1") (pintype "passive"))
      (node (ref "U15") (pin "3") (pintype "passive"))
      (node (ref "U16") (pin "5") (pintype "power_in"))
      (node (ref "U19") (pin "2") (pinfunction "2_2") (pintype "passive"))
      (node (ref "U21") (pin "3") (pinfunction "-_3") (pintype "passive"))
      (node (ref "U25") (pin "11") (pinfunction "A5_11") (pintype "input"))
      (node (ref "U25") (pin "3") (pinfunction "A2_3") (pintype "input"))
      (node (ref "U25") (pin "5") (pinfunction "A3_5") (pintype "input"))
      (node (ref "U25") (pin "7") (pinfunction "GND_7") (pintype "power_in"))
    )
    (net (code "10") (name "Net-(C55-Pad2)") (class "Default")
      (node (ref "C55") (pin "2") (pinfunction "2_2") (pintype "passive"))
      (node (ref "C56") (pin "1") (pinfunction "1_1") (pintype "passive"))
      (node (ref "R73") (pin "1") (pinfunction "1_1") (pintype "passive"))
      (node (ref "TP156") (pin "1") (pinfunction "1_1") (pintype "passive"))
    )
    (net (code "11") (name "Net-(C56-Pad2)") (class "Default")
      (node (ref "C56") (pin "2") (pinfunction "2_2") (pintype "passive"))
      (node (ref "R71") (pin "2") (pinfunction "2_2") (pintype "passive"))
      (node (ref "TP158") (pin "1") (pinfunction "1_1") (pintype "passive"))
    )
    (net (code "12") (name "Net-(C70-Pad1)") (class "Default")
      (node (ref "C70") (pin "1") (pinfunction "1_1") (pintype "passive"))
      (node (ref "CN7") (pin "1") (pinfunction "1_1") (pintype "passive"))
      (node (ref "L6") (pin "2") (pinfunction "2_2") (pintype "passive"))
      (node (ref "TP179") (pin "1") (pinfunction "1_1") (pintype "passive"))
      (node (ref "V4") (pin "2") (pinfunction "2_2") (pintype "passive"))
    )
    (net (code "13") (name "Net-(C70-Pad2)") (class "Default")
      (node (ref "C70") (pin "2") (pinfunction "2_2") (pintype "passive"))
      (node (ref "CN7") (pin "2") (pinfunction "2_2") (pintype "passive"))
      (node (ref "L5") (pin "2") (pinfunction "2_2") (pintype "passive"))
      (node (ref "TP178") (pin "1") (pinfunction "1_1") (pintype "passive"))
      (node (ref "V4") (pin "1") (pinfunction "1_1") (pintype "passive"))
    )
    (net (code "14") (name "Net-(D6-A)") (class "Default")
      (node (ref "D6") (pin "1") (pinfunction "A_1") (pintype "passive"))
      (node (ref "R52") (pin "2") (pinfunction "2_2") (pintype "passive"))
      (node (ref "TP142") (pin "1") (pinfunction "1_1") (pintype "passive"))
      (node (ref "U16") (pin "2") (pintype "passive"))
    )
    (net (code "15") (name "Net-(D6-K)") (class "Default")
      (node (ref "D6") (pin "3") (pinfunction "K_3") (pintype "passive"))
      (node (ref "R52") (pin "1") (pinfunction "1_1") (pintype "passive"))
      (node (ref "TP143") (pin "1") (pinfunction "1_1") (pintype "passive"))
      (node (ref "U17") (pin "8") (pinfunction "Y4_8") (pintype "output"))
    )
    (net (code "16") (name "Net-(D7-A)") (class "Default")
      (node (ref "D7") (pin "1") (pinfunction "A_1") (pintype "passive"))
      (node (ref "R66") (pin "2") (pinfunction "2_2") (pintype "passive"))
      (node (ref "TP145") (pin "1") (pinfunction "1_1") (pintype "passive"))
      (node (ref "U15") (pin "2") (pintype "passive"))
    )
    (net (code "17") (name "Net-(D7-K)") (class "Default")
      (node (ref "D7") (pin "3") (pinfunction "K_3") (pintype "passive"))
      (node (ref "R66") (pin "1") (pinfunction "1_1") (pintype "passive"))
      (node (ref "TP146") (pin "1") (pinfunction "1_1") (pintype "passive"))
      (node (ref "U25") (pin "12") (pinfunction "Y6_12") (pintype "output"))
    )
    (net (code "18") (name "Net-(D8-A)") (class "Default")
      (node (ref "D8") (pin "1") (pinfunction "A_1") (pintype "passive"))
      (node (ref "Q4") (pin "2") (pinfunction "E_2") (pintype "passive"))
      (node (ref "R71") (pin "1") (pinfunction "1_1") (pintype "passive"))
      (node (ref "TP157") (pin "1") (pinfunction "1_1") (pintype "passive"))
    )
    (net (code "19") (name "Net-(D9-A)") (class "Default")
      (node (ref "C69") (pin "2") (pinfunction "2_2") (pintype "passive"))
      (node (ref "D9") (pin "2") (pinfunction "A_2") (pintype "passive"))
      (node (ref "L5") (pin "1") (pinfunction "1_1") (pintype "passive"))
      (node (ref "TP165") (pin "1") (pinfunction "1_1") (pintype "passive"))
      (node (ref "U21") (pin "4") (pinfunction "AC_4") (pintype "passive"))
    )
    (net (code "20") (name "Net-(D10-A)") (class "Default")
      (node (ref "C69") (pin "1") (pinfunction "1_1") (pintype "passive"))
      (node (ref "D10") (pin "2") (pinfunction "A_2") (pintype "passive"))
      (node (ref "L6") (pin "1") (pinfunction "1_1") (pintype "passive"))
      (node (ref "TP164") (pin "1") (pinfunction "1_1") (pintype "passive"))
      (node (ref "U21") (pin "2") (pinfunction "AC_2") (pintype "passive"))
    )
    (net (code "21") (name "Net-(D10-K)") (class "Default")
      (node (ref "C58") (pin "1") (pinfunction "1_1") (pintype "passive"))
      (node (ref "D10") (pin "1") (pinfunction "K_1") (pintype "passive"))
      (node (ref "D9") (pin "1") (pinfunction "K_1") (pintype "passive"))
      (node (ref "TP163") (pin "1") (pinfunction "1_1") (pintype "passive"))
      (node (ref "U20") (pin "3") (pinfunction "Vin_3") (pintype "passive"))
    )
    (net (code "22") (name "Net-(Q2-D)") (class "Default")
      (node (ref "Q2") (pin "3") (pinfunction "D_3") (pintype "passive"))
      (node (ref "R72") (pin "1") (pinfunction "1_1") (pintype "passive"))
      (node (ref "R75") (pin "1") (pinfunction "1_1") (pintype "passive"))
      (node (ref "TP151") (pin "1") (pinfunction "1_1") (pintype "passive"))
    )
    (net (code "23") (name "Net-(Q2-G)") (class "Default")
      (node (ref "Q2") (pin "1") (pinfunction "G_1") (pintype "passive"))
      (node (ref "R77") (pin "2") (pinfunction "2_2") (pintype "passive"))
      (node (ref "TP150") (pin "1") (pinfunction "1_1") (pintype "passive"))
      (node (ref "U25") (pin "8") (pinfunction "Y4_8") (pintype "output"))
    )
    (net (code "24") (name "Net-(Q3-B)") (class "Default")
      (node (ref "C54") (pin "2") (pinfunction "2_2") (pintype "passive"))
      (node (ref "Q3") (pin "1") (pinfunction "B_1") (pintype "passive"))
      (node (ref "R75") (pin "2") (pinfunction "2_2") (pintype "passive"))
      (node (ref "TP152") (pin "1") (pinfunction "1_1") (pintype "passive"))
    )
    (net (code "25") (name "Net-(Q3-E)") (class "Default")
      (node (ref "Q3") (pin "2") (pinfunction "E_2") (pintype "passive"))
      (node (ref "Q5") (pin "1") (pinfunction "B_1") (pintype "passive"))
      (node (ref "TP153") (pin "1") (pinfunction "1_1") (pintype "passive"))
    )
    (net (code "26") (name "Net-(Q4-C)") (class "Default")
      (node (ref "Q4") (pin "3") (pinfunction "C_3") (pintype "passive"))
      (node (ref "R69") (pin "2") (pinfunction "2_2") (pintype "passive"))
      (node (ref "TP148") (pin "1") (pinfunction "1_1") (pintype "passive"))
      (node (ref "U25") (pin "1") (pinfunction "A1_1") (pintype "input"))
    )
    (net (code "27") (name "Net-(Q5-E)") (class "Default")
      (node (ref "Q5") (pin "3") (pinfunction "E_3") (pintype "passive"))
      (node (ref "R76") (pin "1") (pinfunction "1_1") (pintype "passive"))
      (node (ref "TP187") (pin "1") (pinfunction "1_1") (pintype "passive"))
    )
    (net (code "28") (name "Net-(R65-Pad1)") (class "Default")
      (node (ref "R65") (pin "1") (pinfunction "1_1") (pintype "passive"))
      (node (ref "TP161") (pin "1") (pinfunction "1_1") (pintype "passive"))
      (node (ref "U19") (pin "1") (pinfunction "1_1") (pintype "passive"))
    )
    (net (code "29") (name "Net-(TVS1-A)") (class "Default")
      (node (ref "C68") (pin "1") (pinfunction "1_1") (pintype "passive"))
      (node (ref "CN7") (pin "3") (pinfunction "3_3") (pintype "passive"))
      (node (ref "TP177") (pin "1") (pinfunction "1_1") (pintype "passive"))
      (node (ref "TVS1") (pin "2") (pinfunction "A_2") (pintype "passive"))
      (node (ref "U28") (pin "3") (pinfunction "PSG_3") (pintype "passive"))
    )
    (net (code "30") (name "Net-(TVS1-K)") (class "Default")
      (node (ref "C68") (pin "2") (pinfunction "2_2") (pintype "passive"))
      (node (ref "CN7") (pin "4") (pinfunction "4_4") (pintype "passive"))
      (node (ref "TP175") (pin "1") (pinfunction "1_1") (pintype "passive"))
      (node (ref "TVS1") (pin "1") (pinfunction "K_1") (pintype "passive"))
      (node (ref "U28") (pin "1") (pinfunction "B_1") (pintype "passive"))
    )
    (net (code "31") (name "Net-(U17C-A3)") (class "Default")
      (node (ref "R50") (pin "2") (pinfunction "2_2") (pintype "passive"))
      (node (ref "TP144") (pin "1") (pinfunction "1_1") (pintype "passive"))
      (node (ref "U15") (pin "6") (pintype "passive"))
      (node (ref "U17") (pin "5") (pinfunction "A3_5") (pintype "input"))
    )
    (net (code "32") (name "Net-(U17D-A4)") (class "Default")
      (node (ref "TP141") (pin "1") (pinfunction "1_1") (pintype "passive"))
      (node (ref "U17") (pin "9") (pinfunction "A4_9") (pintype "input"))
      (node (ref "U23") (pin "4") (pinfunction "Y_4") (pintype "output"))
    )
    (net (code "33") (name "Net-(U20-ADJ)") (class "Default")
      (node (ref "R67") (pin "2") (pinfunction "2_2") (pintype "passive"))
      (node (ref "R68") (pin "1") (pinfunction "1_1") (pintype "passive"))
      (node (ref "TP162") (pin "1") (pinfunction "1_1") (pintype "passive"))
      (node (ref "U20") (pin "1") (pinfunction "ADJ_1") (pintype "passive"))
    )
    (net (code "34") (name "Net-(U21-+)") (class "Default")
      (node (ref "R72") (pin "2") (pinfunction "2_2") (pintype "passive"))
      (node (ref "R73") (pin "2") (pinfunction "2_2") (pintype "passive"))
      (node (ref "R74") (pin "2") (pinfunction "2_2") (pintype "passive"))
      (node (ref "R76") (pin "2") (pinfunction "2_2") (pintype "passive"))
      (node (ref "TP154") (pin "1") (pinfunction "1_1") (pintype "passive"))
      (node (ref "U21") (pin "1") (pinfunction "+_1") (pintype "passive"))
    )
    (net (code "35") (name "Net-(U22-AAM)") (class "Default")
      (node (ref "R96") (pin "2") (pinfunction "2_2") (pintype "passive"))
      (node (ref "TP185") (pin "1") (pinfunction "1_1") (pintype "passive"))
      (node (ref "U22") (pin "18") (pinfunction "AAM_18") (pintype "passive"))
    )
    (net (code "36") (name "Net-(U22-EN)") (class "Default")
      (node (ref "R48") (pin "2") (pinfunction "2_2") (pintype "passive"))
      (node (ref "TP184") (pin "1") (pinfunction "1_1") (pintype "passive"))
      (node (ref "U22") (pin "17") (pinfunction "EN_17") (pintype "passive"))
    )
    (net (code "37") (name "Net-(U22-FB)") (class "Default")
      (node (ref "R94") (pin "2") (pinfunction "2_2") (pintype "passive"))
      (node (ref "R95") (pin "1") (pinfunction "1_1") (pintype "passive"))
      (node (ref "TP186") (pin "1") (pinfunction "1_1") (pintype "passive"))
      (node (ref "U22") (pin "1") (pinfunction "FB_1") (pintype "passive"))
    )
    (net (code "38") (name "Net-(U25A-Y1)") (class "Default")
      (node (ref "TP147") (pin "1") (pinfunction "1_1") (pintype "passive"))
      (node (ref "U25") (pin "13") (pinfunction "A6_13") (pintype "input"))
      (node (ref "U25") (pin "2") (pinfunction "Y1_2") (pintype "output"))
    )
    (net (code "39") (name "Net-(U25D-A4)") (class "Default")
      (node (ref "R70") (pin "2") (pinfunction "2_2") (pintype "passive"))
      (node (ref "TP149") (pin "1") (pinfunction "1_1") (pintype "passive"))
      (node (ref "U16") (pin "6") (pintype "passive"))
      (node (ref "U25") (pin "9") (pinfunction "A4_9") (pintype "input"))
    )
    (net (code "40") (name "unconnected-(U17A-Y1-Pad2)") (class "Default")
      (node (ref "U17") (pin "2") (pinfunction "Y1_2") (pintype "output"))
    )
    (net (code "41") (name "unconnected-(U17B-Y2-Pad4)") (class "Default")
      (node (ref "U17") (pin "4") (pinfunction "Y2_4") (pintype "output"))
    )
    (net (code "42") (name "unconnected-(U17E-Y5-Pad10)") (class "Default")
      (node (ref "U17") (pin "10") (pinfunction "Y5_10") (pintype "output"))
    )
    (net (code "43") (name "unconnected-(U17F-Y6-Pad12)") (class "Default")
      (node (ref "U17") (pin "12") (pinfunction "Y6_12") (pintype "output"))
    )
    (net (code "44") (name "unconnected-(U22-BST-Pad11)") (class "Default")
      (node (ref "U22") (pin "11") (pinfunction "BST_11") (pintype "passive"))
    )
    (net (code "45") (name "unconnected-(U22-SW-Pad4)") (class "Default")
      (node (ref "U22") (pin "4") (pinfunction "SW_4") (pintype "passive"))
    )
    (net (code "46") (name "unconnected-(U22-SW-Pad5)") (class "Default")
      (node (ref "U22") (pin "5") (pinfunction "SW_5") (pintype "passive"))
    )
    (net (code "47") (name "unconnected-(U22-SW-Pad6)") (class "Default")
      (node (ref "U22") (pin "6") (pinfunction "SW_6") (pintype "passive"))
    )
    (net (code "48") (name "unconnected-(U22-Vcc-Pad2)") (class "Default")
      (node (ref "U22") (pin "2") (pinfunction "Vcc_2") (pintype "passive"))
    )
    (net (code "49") (name "unconnected-(U25B-Y2-Pad4)") (class "Default")
      (node (ref "U25") (pin "4") (pinfunction "Y2_4") (pintype "output"))
    )
    (net (code "50") (name "unconnected-(U25C-Y3-Pad6)") (class "Default")
      (node (ref "U25") (pin "6") (pinfunction "Y3_6") (pintype "output"))
    )
    (net (code "51") (name "unconnected-(U25E-Y5-Pad10)") (class "Default")
      (node (ref "U25") (pin "10") (pinfunction "Y5_10") (pintype "output"))
    )
  )
)
